# Connectors.net
KiCad netlist of a schematic drawn in Altium Designer
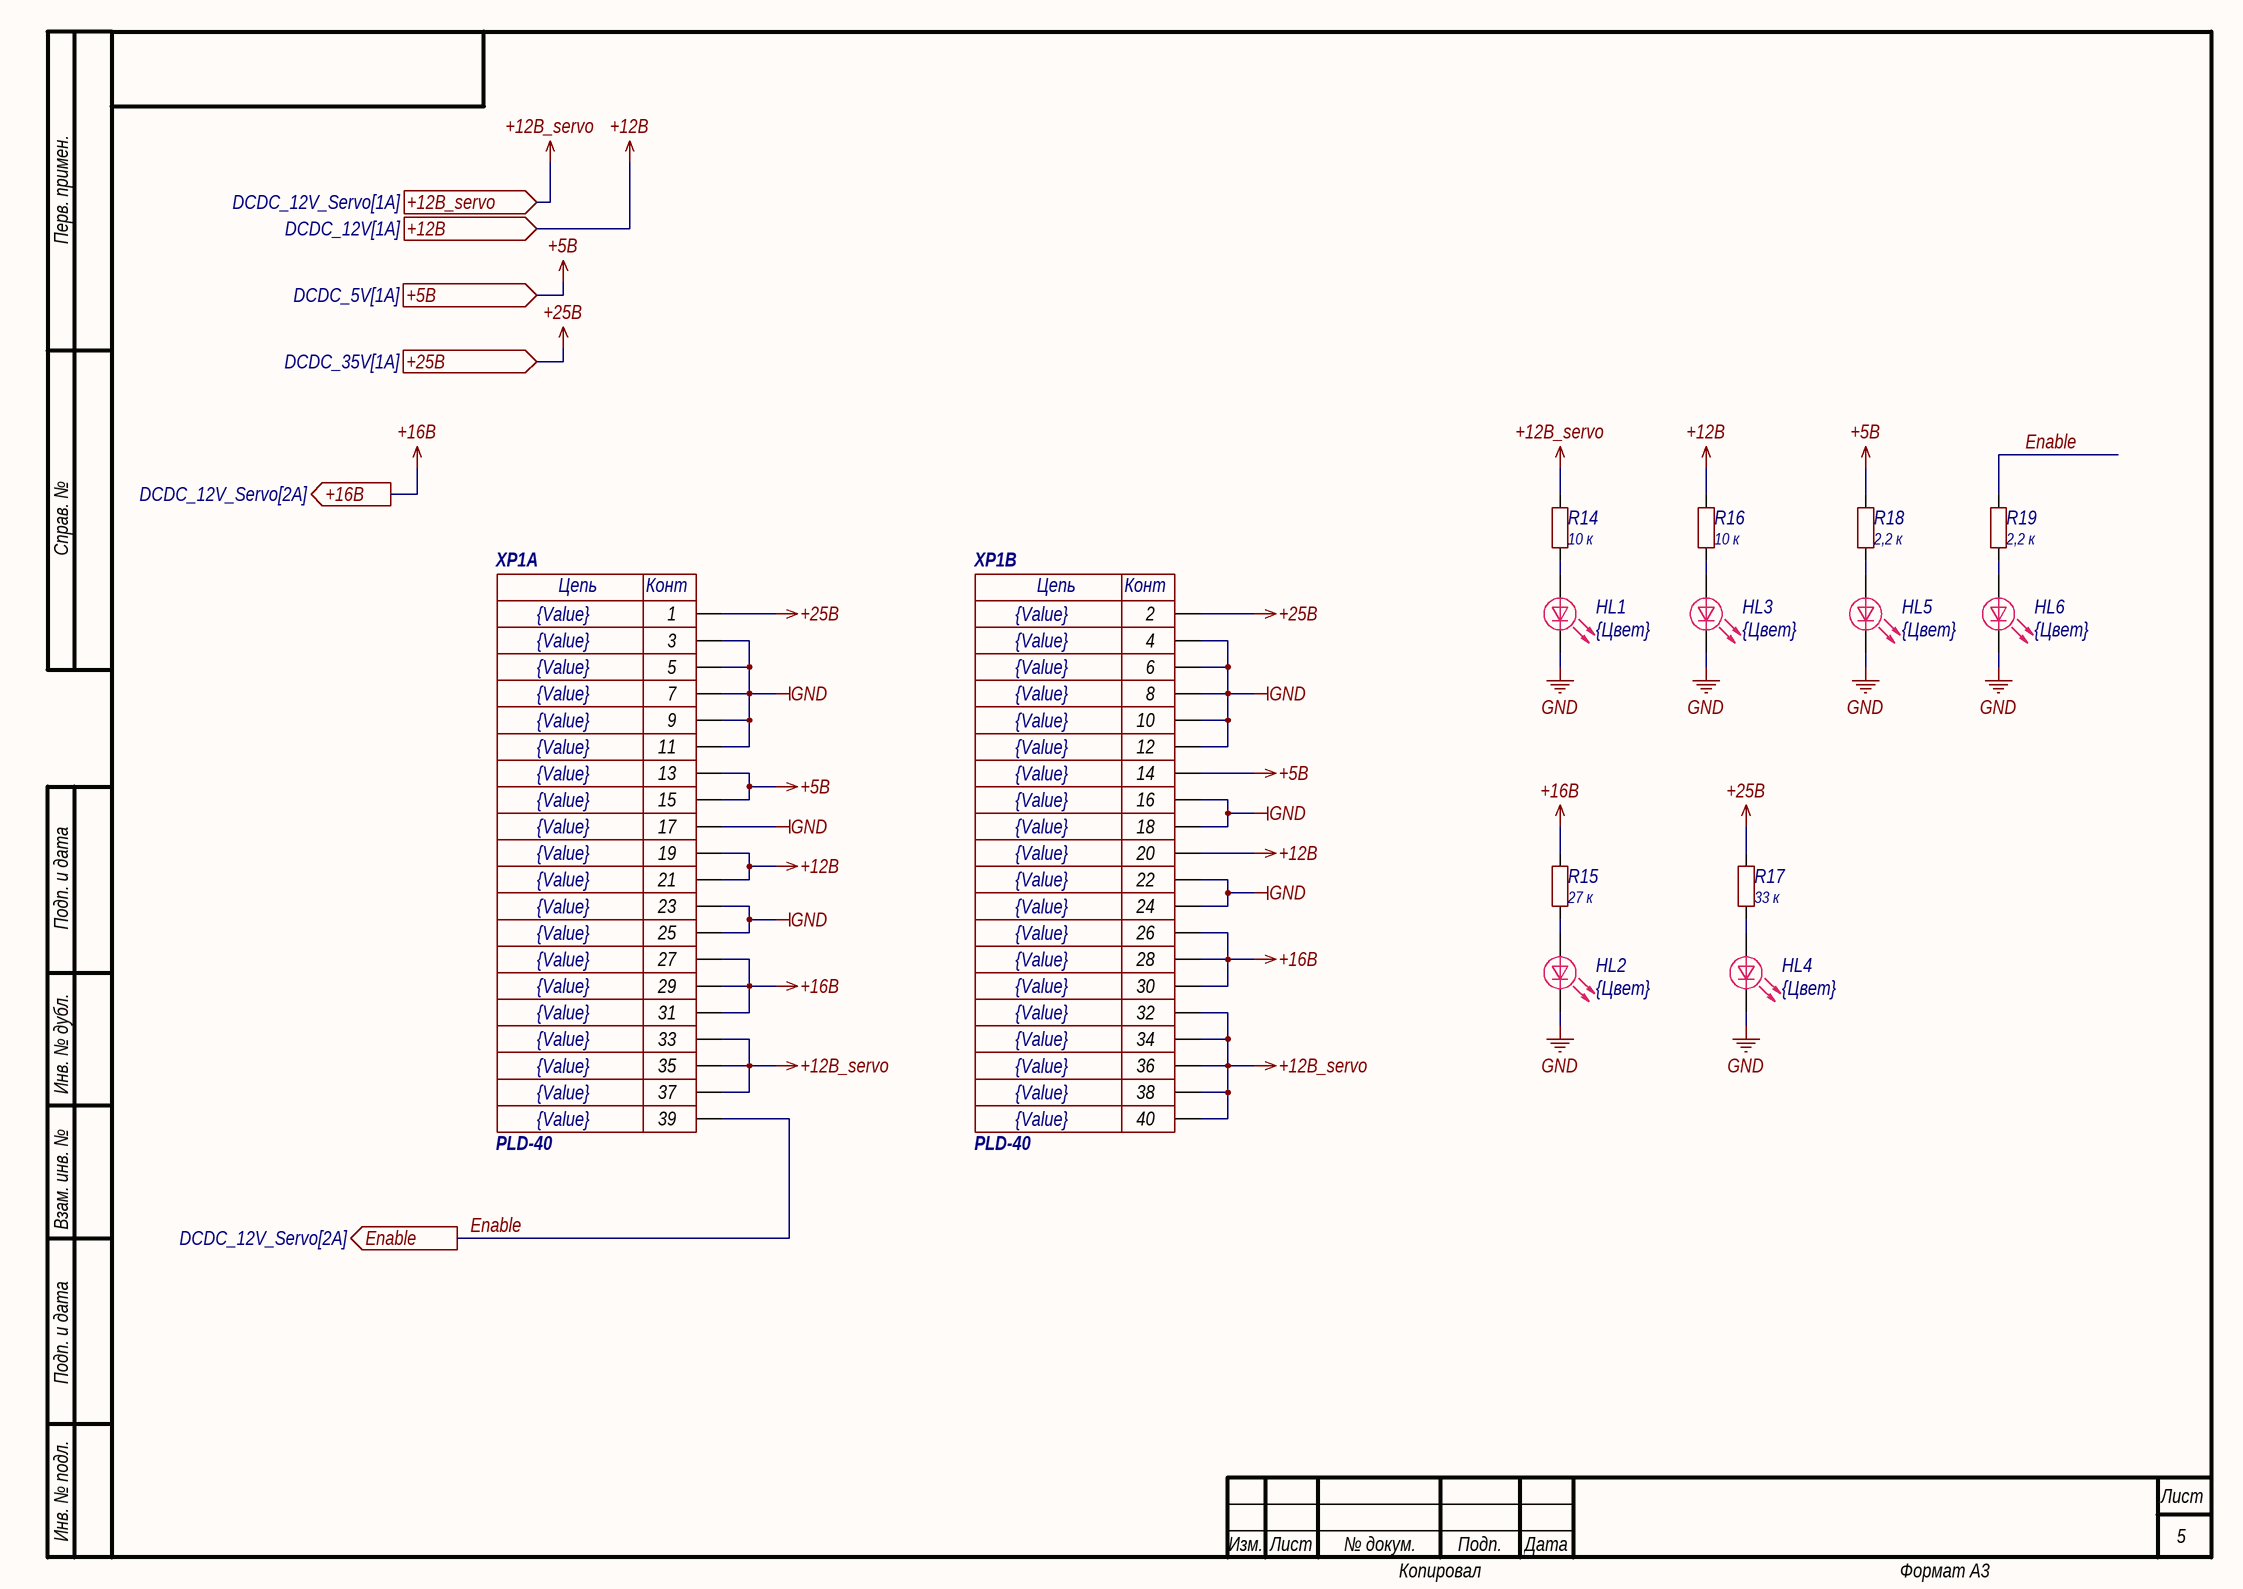
[diagram p0: Connectors.SchDoc]

(export (version "E")
  (design (tool "Eeschema 10.0.6"))
  (components
    (comp (ref "HL1")
      (value "LED")
      (footprint "0805D")
      (description "Светодиод")
      (fields (field (name "COLOR") "{Цвет}"))
      (libsource (lib "Hydrolib") (part "LED"))
    )
    (comp (ref "HL2")
      (value "LED")
      (footprint "0805D")
      (description "Светодиод")
      (fields (field (name "COLOR") "{Цвет}"))
      (libsource (lib "Hydrolib") (part "LED"))
    )
    (comp (ref "HL3")
      (value "LED")
      (footprint "0805D")
      (description "Светодиод")
      (fields (field (name "COLOR") "{Цвет}"))
      (libsource (lib "Hydrolib") (part "LED"))
    )
    (comp (ref "HL4")
      (value "LED")
      (footprint "0805D")
      (description "Светодиод")
      (fields (field (name "COLOR") "{Цвет}"))
      (libsource (lib "Hydrolib") (part "LED"))
    )
    (comp (ref "HL5")
      (value "LED")
      (footprint "0805D")
      (description "Светодиод")
      (fields (field (name "COLOR") "{Цвет}"))
      (libsource (lib "Hydrolib") (part "LED"))
    )
    (comp (ref "HL6")
      (value "LED")
      (footprint "0805D")
      (description "Светодиод")
      (fields (field (name "COLOR") "{Цвет}"))
      (libsource (lib "Hydrolib") (part "LED"))
    )
    (comp (ref "R14")
      (value "10 к")
      (footprint "0603R")
      (description "Резистор номиналом 10 кОм и точностью 1%")
      (fields (field (name "PART NUMBER") "Resistor_10k_1_0603") (field (name "TOLERANCE") "1%"))
      (libsource (lib "Hydrolib") (part "Resistor"))
    )
    (comp (ref "R15")
      (value "27 к")
      (footprint "0603R")
      (description "Резистор номиналом 27 кОм и точностью 1%")
      (fields (field (name "PART NUMBER") "Resistor_27k_1_0603") (field (name "TOLERANCE") "1%"))
      (libsource (lib "Hydrolib") (part "Resistor"))
    )
    (comp (ref "R16")
      (value "10 к")
      (footprint "0603R")
      (description "Резистор номиналом 10 кОм и точностью 1%")
      (fields (field (name "PART NUMBER") "Resistor_10k_1_0603") (field (name "TOLERANCE") "1%"))
      (libsource (lib "Hydrolib") (part "Resistor"))
    )
    (comp (ref "R17")
      (value "33 к")
      (footprint "0603R")
      (description "Резистор номиналом 33 кОм и точностью 1%")
      (fields (field (name "PART NUMBER") "Resistor_33k_1_0603") (field (name "TOLERANCE") "1%"))
      (libsource (lib "Hydrolib") (part "Resistor"))
    )
    (comp (ref "R18")
      (value "2,2 к")
      (footprint "0603R")
      (description "Резистор номиналом 2,2 кОм и точностью 1%")
      (fields (field (name "PART NUMBER") "Resistor_2.2k_1_0603") (field (name "TOLERANCE") "1%"))
      (libsource (lib "Hydrolib") (part "Resistor"))
    )
    (comp (ref "R19")
      (value "2,2 к")
      (footprint "0603R")
      (description "Резистор номиналом 2,2 кОм и точностью 1%")
      (fields (field (name "PART NUMBER") "Resistor_2.2k_1_0603") (field (name "TOLERANCE") "1%"))
      (libsource (lib "Hydrolib") (part "Resistor"))
    )
    (comp (ref "XP1")
      (value "PLD-40")
      (footprint "PLD40")
      (description "Гребенка 40 пинов")
      (fields
        (field (name "VALUE17") "{Value}")
        (field (name "VALUE20") "{Value}")
        (field (name "VALUE19") "{Value}")
        (field (name "VALUE18") "{Value}")
        (field (name "VALUE16") "{Value}")
        (field (name "VALUE15") "{Value}")
        (field (name "VALUE14") "{Value}")
        (field (name "VALUE13") "{Value}")
        (field (name "VALUE12") "{Value}")
        (field (name "VALUE11") "{Value}")
        (field (name "VALUE10") "{Value}")
        (field (name "VALUE9") "{Value}")
        (field (name "VALUE8") "{Value}")
        (field (name "VALUE7") "{Value}")
        (field (name "VALUE6") "{Value}")
        (field (name "VALUE5") "{Value}")
        (field (name "VALUE4") "{Value}")
        (field (name "VALUE3") "{Value}")
        (field (name "VALUE2") "{Value}")
        (field (name "VALUE1") "{Value}")
      )
      (libsource (lib "Hydrolib") (part "Conn_40pin_double"))
    )
  )
  (nets
    (net (code "1") (name "+5В") (class "Default")
      (node (ref "R18") (pin "2") (pinfunction "2_2") (pintype "passive"))
      (node (ref "XP1") (pin "13") (pinfunction "13_13") (pintype "passive"))
      (node (ref "XP1") (pin "14") (pinfunction "14_14") (pintype "passive"))
      (node (ref "XP1") (pin "15") (pinfunction "15_15") (pintype "passive"))
    )
    (net (code "2") (name "+12В") (class "Default")
      (node (ref "R16") (pin "2") (pinfunction "2_2") (pintype "passive"))
      (node (ref "XP1") (pin "19") (pinfunction "19_19") (pintype "passive"))
      (node (ref "XP1") (pin "20") (pinfunction "20_20") (pintype "passive"))
      (node (ref "XP1") (pin "21") (pinfunction "21_21") (pintype "passive"))
    )
    (net (code "3") (name "+12В_servo") (class "Default")
      (node (ref "R14") (pin "2") (pinfunction "2_2") (pintype "passive"))
      (node (ref "XP1") (pin "32") (pinfunction "32_32") (pintype "passive"))
      (node (ref "XP1") (pin "33") (pinfunction "33_33") (pintype "passive"))
      (node (ref "XP1") (pin "34") (pinfunction "34_34") (pintype "passive"))
      (node (ref "XP1") (pin "35") (pinfunction "35_35") (pintype "passive"))
      (node (ref "XP1") (pin "36") (pinfunction "36_36") (pintype "passive"))
      (node (ref "XP1") (pin "37") (pinfunction "37_37") (pintype "passive"))
      (node (ref "XP1") (pin "38") (pinfunction "38_38") (pintype "passive"))
      (node (ref "XP1") (pin "40") (pinfunction "40_40") (pintype "passive"))
    )
    (net (code "4") (name "+16В") (class "Default")
      (node (ref "R15") (pin "2") (pinfunction "2_2") (pintype "passive"))
      (node (ref "XP1") (pin "26") (pinfunction "26_26") (pintype "passive"))
      (node (ref "XP1") (pin "27") (pinfunction "27_27") (pintype "passive"))
      (node (ref "XP1") (pin "28") (pinfunction "28_28") (pintype "passive"))
      (node (ref "XP1") (pin "29") (pinfunction "29_29") (pintype "passive"))
      (node (ref "XP1") (pin "30") (pinfunction "30_30") (pintype "passive"))
      (node (ref "XP1") (pin "31") (pinfunction "31_31") (pintype "passive"))
    )
    (net (code "5") (name "+25В") (class "Default")
      (node (ref "R17") (pin "2") (pinfunction "2_2") (pintype "passive"))
      (node (ref "XP1") (pin "1") (pinfunction "1_1") (pintype "passive"))
      (node (ref "XP1") (pin "2") (pinfunction "2_2") (pintype "passive"))
    )
    (net (code "6") (name "/Enable") (class "Default")
      (node (ref "R19") (pin "2") (pinfunction "2_2") (pintype "passive"))
      (node (ref "XP1") (pin "39") (pinfunction "39_39") (pintype "passive"))
    )
    (net (code "7") (name "GND") (class "Default")
      (node (ref "HL1") (pin "2") (pinfunction "2_2") (pintype "passive"))
      (node (ref "HL2") (pin "2") (pinfunction "2_2") (pintype "passive"))
      (node (ref "HL3") (pin "2") (pinfunction "2_2") (pintype "passive"))
      (node (ref "HL4") (pin "2") (pinfunction "2_2") (pintype "passive"))
      (node (ref "HL5") (pin "2") (pinfunction "2_2") (pintype "passive"))
      (node (ref "HL6") (pin "2") (pinfunction "2_2") (pintype "passive"))
      (node (ref "XP1") (pin "10") (pinfunction "10_10") (pintype "passive"))
      (node (ref "XP1") (pin "11") (pinfunction "11_11") (pintype "passive"))
      (node (ref "XP1") (pin "12") (pinfunction "12_12") (pintype "passive"))
      (node (ref "XP1") (pin "16") (pinfunction "16_16") (pintype "passive"))
      (node (ref "XP1") (pin "17") (pinfunction "17_17") (pintype "passive"))
      (node (ref "XP1") (pin "18") (pinfunction "18_18") (pintype "passive"))
      (node (ref "XP1") (pin "22") (pinfunction "22_22") (pintype "passive"))
      (node (ref "XP1") (pin "23") (pinfunction "23_23") (pintype "passive"))
      (node (ref "XP1") (pin "24") (pinfunction "24_24") (pintype "passive"))
      (node (ref "XP1") (pin "25") (pinfunction "25_25") (pintype "passive"))
      (node (ref "XP1") (pin "3") (pinfunction "3_3") (pintype "passive"))
      (node (ref "XP1") (pin "4") (pinfunction "4_4") (pintype "passive"))
      (node (ref "XP1") (pin "5") (pinfunction "5_5") (pintype "passive"))
      (node (ref "XP1") (pin "6") (pinfunction "6_6") (pintype "passive"))
      (node (ref "XP1") (pin "7") (pinfunction "7_7") (pintype "passive"))
      (node (ref "XP1") (pin "8") (pinfunction "8_8") (pintype "passive"))
      (node (ref "XP1") (pin "9") (pinfunction "9_9") (pintype "passive"))
    )
    (net (code "8") (name "Net-(HL1-Pad1)") (class "Default")
      (node (ref "HL1") (pin "1") (pinfunction "1_1") (pintype "passive"))
      (node (ref "R14") (pin "1") (pinfunction "1_1") (pintype "passive"))
    )
    (net (code "9") (name "Net-(HL2-Pad1)") (class "Default")
      (node (ref "HL2") (pin "1") (pinfunction "1_1") (pintype "passive"))
      (node (ref "R15") (pin "1") (pinfunction "1_1") (pintype "passive"))
    )
    (net (code "10") (name "Net-(HL3-Pad1)") (class "Default")
      (node (ref "HL3") (pin "1") (pinfunction "1_1") (pintype "passive"))
      (node (ref "R16") (pin "1") (pinfunction "1_1") (pintype "passive"))
    )
    (net (code "11") (name "Net-(HL4-Pad1)") (class "Default")
      (node (ref "HL4") (pin "1") (pinfunction "1_1") (pintype "passive"))
      (node (ref "R17") (pin "1") (pinfunction "1_1") (pintype "passive"))
    )
    (net (code "12") (name "Net-(HL5-Pad1)") (class "Default")
      (node (ref "HL5") (pin "1") (pinfunction "1_1") (pintype "passive"))
      (node (ref "R18") (pin "1") (pinfunction "1_1") (pintype "passive"))
    )
    (net (code "13") (name "Net-(HL6-Pad1)") (class "Default")
      (node (ref "HL6") (pin "1") (pinfunction "1_1") (pintype "passive"))
      (node (ref "R19") (pin "1") (pinfunction "1_1") (pintype "passive"))
    )
  )
)
